# devBoard.net
KiCad netlist of a schematic drawn in Altium Designer
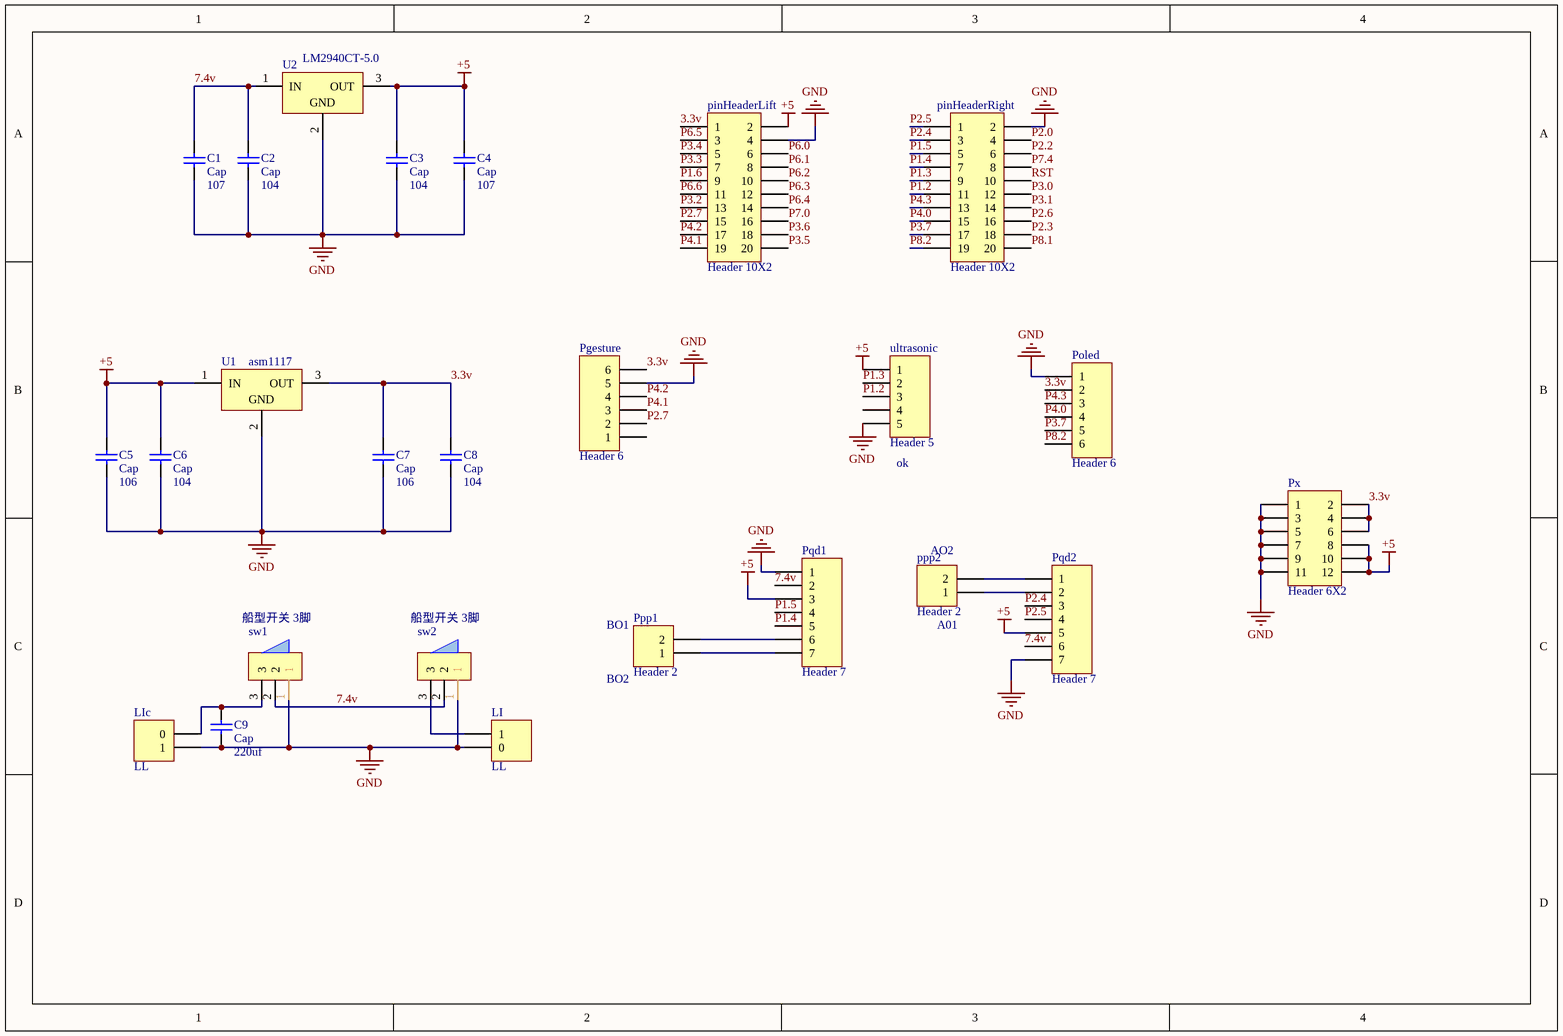
[diagram p0: devBoard.SchDoc]

(export (version "E")
  (design (tool "Eeschema 10.0.6"))
  (components
    (comp (ref "C1")
      (value "Cap")
      (footprint "RAD-0.3")
      (description "Capacitor")
      (fields (field (name "ALTIUM_VALUE") "107") (field (name "PUBLISHER") "Altium Limited"))
      (libsource (lib "Miscellaneous Devices") (part "Cap"))
    )
    (comp (ref "C2")
      (value "Cap")
      (footprint "RAD-0.3")
      (description "Capacitor")
      (fields (field (name "ALTIUM_VALUE") "104") (field (name "PUBLISHER") "Altium Limited"))
      (libsource (lib "Miscellaneous Devices") (part "Cap"))
    )
    (comp (ref "C3")
      (value "Cap")
      (footprint "RAD-0.3")
      (description "Capacitor")
      (fields (field (name "ALTIUM_VALUE") "104") (field (name "PUBLISHER") "Altium Limited"))
      (libsource (lib "Miscellaneous Devices") (part "Cap"))
    )
    (comp (ref "C4")
      (value "Cap")
      (footprint "RAD-0.3")
      (description "Capacitor")
      (fields (field (name "ALTIUM_VALUE") "107") (field (name "PUBLISHER") "Altium Limited"))
      (libsource (lib "Miscellaneous Devices") (part "Cap"))
    )
    (comp (ref "C5")
      (value "Cap")
      (footprint "RAD-0.3")
      (description "Capacitor")
      (fields (field (name "ALTIUM_VALUE") "106") (field (name "PUBLISHER") "Altium Limited"))
      (libsource (lib "Miscellaneous Devices") (part "Cap"))
    )
    (comp (ref "C6")
      (value "Cap")
      (footprint "RAD-0.3")
      (description "Capacitor")
      (fields (field (name "ALTIUM_VALUE") "104") (field (name "PUBLISHER") "Altium Limited"))
      (libsource (lib "Miscellaneous Devices") (part "Cap"))
    )
    (comp (ref "C7")
      (value "Cap")
      (footprint "RAD-0.3")
      (description "Capacitor")
      (fields (field (name "ALTIUM_VALUE") "106") (field (name "PUBLISHER") "Altium Limited"))
      (libsource (lib "Miscellaneous Devices") (part "Cap"))
    )
    (comp (ref "C8")
      (value "Cap")
      (footprint "RAD-0.3")
      (description "Capacitor")
      (fields (field (name "ALTIUM_VALUE") "104") (field (name "PUBLISHER") "Altium Limited"))
      (libsource (lib "Miscellaneous Devices") (part "Cap"))
    )
    (comp (ref "C9")
      (value "Cap")
      (footprint "RAD-0.3")
      (description "Capacitor")
      (fields (field (name "ALTIUM_VALUE") "220uf") (field (name "PUBLISHER") "Altium Limited"))
      (libsource (lib "Miscellaneous Devices") (part "Cap"))
    )
    (comp (ref "LI")
      (value "LL")
      (footprint "Con 2接线端子")
      (description "Header, 2-Pin")
      (fields (field (name "PUBLISHER") "Altium Limited"))
      (libsource (lib "") (part "Header 2_2"))
    )
    (comp (ref "LIc")
      (value "LL")
      (footprint "Con 2接线端子")
      (description "Header, 2-Pin")
      (fields (field (name "PUBLISHER") "Altium Limited"))
      (libsource (lib "") (part "Header 2_1"))
    )
    (comp (ref "Pgesture")
      (value "Header 6")
      (footprint "HDR1X6")
      (description "Header, 6-Pin")
      (fields (field (name "PUBLISHER") "Altium Limited"))
      (libsource (lib "") (part "Header 6_1"))
    )
    (comp (ref "pinHeaderLift")
      (value "Header 10X2")
      (footprint "HDR2X10")
      (description "Header, 10-Pin, Dual row")
      (fields (field (name "PUBLISHER") "Altium Limited"))
      (libsource (lib "Miscellaneous Connectors") (part "Header 10X2"))
    )
    (comp (ref "pinHeaderRight")
      (value "Header 10X2")
      (footprint "HDR2X10")
      (description "Header, 10-Pin, Dual row")
      (fields (field (name "PUBLISHER") "Altium Limited"))
      (libsource (lib "Miscellaneous Connectors") (part "Header 10X2"))
    )
    (comp (ref "Poled")
      (value "Header 6")
      (footprint "HDR1X6")
      (description "Header, 6-Pin")
      (fields (field (name "PUBLISHER") "Altium Limited"))
      (libsource (lib "Miscellaneous Connectors") (part "Header 6"))
    )
    (comp (ref "Ppp1")
      (value "Header 2")
      (footprint "HDR1X2")
      (description "Header, 2-Pin")
      (fields (field (name "PUBLISHER") "Altium Limited"))
      (libsource (lib "Miscellaneous Connectors") (part "Header 2"))
    )
    (comp (ref "ppp2")
      (value "Header 2")
      (footprint "HDR1X2")
      (description "Header, 2-Pin")
      (fields (field (name "PUBLISHER") "Altium Limited"))
      (libsource (lib "Miscellaneous Connectors") (part "Header 2"))
    )
    (comp (ref "Pqd1")
      (value "Header 7")
      (footprint "HDR1X7")
      (description "Header, 7-Pin")
      (fields (field (name "PUBLISHER") "Altium Limited"))
      (libsource (lib "Miscellaneous Connectors") (part "Header 7"))
    )
    (comp (ref "Pqd2")
      (value "Header 7")
      (footprint "HDR1X7")
      (description "Header, 7-Pin")
      (fields (field (name "PUBLISHER") "Altium Limited"))
      (libsource (lib "Miscellaneous Connectors") (part "Header 7"))
    )
    (comp (ref "Px")
      (value "Header 6X2")
      (footprint "HDR2X6")
      (description "Header, 6-Pin, Dual row")
      (fields (field (name "PUBLISHER") "Altium Limited"))
      (libsource (lib "Miscellaneous Connectors") (part "Header 6X2"))
    )
    (comp (ref "sw1")
      (value "船型开关 3脚")
      (footprint "船型开关 3脚")
      (libsource (lib "altium-import") (part "root_0_船型开关 3脚_"))
    )
    (comp (ref "sw2")
      (value "船型开关 3脚")
      (footprint "船型开关 3脚")
      (libsource (lib "altium-import") (part "root_0_船型开关 3脚_"))
    )
    (comp (ref "U1")
      (value "asm1117")
      (footprint "T03B")
      (description "1A 5V")
      (fields (field (name "PUBLISHER") "Altium Limited"))
      (libsource (lib "TSLone") (part "LM2940CT-5.0"))
    )
    (comp (ref "U2")
      (value "LM2940CT-5.0")
      (footprint "T03B")
      (description "1A 5V")
      (fields (field (name "PUBLISHER") "Altium Limited"))
      (libsource (lib "TSLone") (part "LM2940CT-5.0"))
    )
    (comp (ref "ultrasonic")
      (value "Header 5")
      (footprint "HDR1X5")
      (description "Header, 5-Pin")
      (fields (field (name "PUBLISHER") "Altium Limited"))
      (libsource (lib "Miscellaneous Connectors") (part "Header 5"))
    )
  )
  (nets
    (net (code "1") (name "+5") (class "Default")
      (node (ref "C3") (pin "2") (pinfunction "2_2") (pintype "passive"))
      (node (ref "C4") (pin "2") (pinfunction "2_2") (pintype "passive"))
      (node (ref "C5") (pin "2") (pinfunction "2_2") (pintype "passive"))
      (node (ref "C6") (pin "2") (pinfunction "2_2") (pintype "passive"))
      (node (ref "Pqd1") (pin "3") (pinfunction "3_3") (pintype "passive"))
      (node (ref "Pqd2") (pin "5") (pinfunction "5_5") (pintype "passive"))
      (node (ref "Px") (pin "10") (pinfunction "10_10") (pintype "passive"))
      (node (ref "Px") (pin "12") (pinfunction "12_12") (pintype "passive"))
      (node (ref "Px") (pin "8") (pinfunction "8_8") (pintype "passive"))
      (node (ref "U1") (pin "1") (pinfunction "IN_1") (pintype "power_in"))
      (node (ref "U2") (pin "3") (pinfunction "OUT_3") (pintype "power_in"))
      (node (ref "pinHeaderLift") (pin "2") (pinfunction "2_2") (pintype "passive"))
      (node (ref "ultrasonic") (pin "1") (pinfunction "1_1") (pintype "passive"))
    )
    (net (code "2") (name "/3.3v") (class "Default")
      (node (ref "C7") (pin "2") (pinfunction "2_2") (pintype "passive"))
      (node (ref "C8") (pin "2") (pinfunction "2_2") (pintype "passive"))
      (node (ref "Pgesture") (pin "6") (pinfunction "6_6") (pintype "passive"))
      (node (ref "Poled") (pin "2") (pinfunction "2_2") (pintype "passive"))
      (node (ref "Px") (pin "2") (pinfunction "2_2") (pintype "passive"))
      (node (ref "Px") (pin "4") (pinfunction "4_4") (pintype "passive"))
      (node (ref "Px") (pin "6") (pinfunction "6_6") (pintype "passive"))
      (node (ref "U1") (pin "3") (pinfunction "OUT_3") (pintype "power_in"))
      (node (ref "pinHeaderLift") (pin "1") (pinfunction "1_1") (pintype "passive"))
    )
    (net (code "3") (name "/7.4v") (class "Default")
      (node (ref "C1") (pin "2") (pinfunction "2_2") (pintype "passive"))
      (node (ref "C2") (pin "2") (pinfunction "2_2") (pintype "passive"))
      (node (ref "Pqd1") (pin "2") (pinfunction "2_2") (pintype "passive"))
      (node (ref "Pqd2") (pin "6") (pinfunction "6_6") (pintype "passive"))
      (node (ref "U2") (pin "1") (pinfunction "IN_1") (pintype "power_in"))
      (node (ref "sw1") (pin "2") (pinfunction "2_2") (pintype "passive"))
      (node (ref "sw2") (pin "2") (pinfunction "2_2") (pintype "passive"))
    )
    (net (code "4") (name "/P1.2") (class "Default")
      (node (ref "pinHeaderRight") (pin "11") (pinfunction "11_11") (pintype "passive"))
      (node (ref "ultrasonic") (pin "3") (pinfunction "3_3") (pintype "passive"))
    )
    (net (code "5") (name "/P1.3") (class "Default")
      (node (ref "pinHeaderRight") (pin "9") (pinfunction "9_9") (pintype "passive"))
      (node (ref "ultrasonic") (pin "2") (pinfunction "2_2") (pintype "passive"))
    )
    (net (code "6") (name "/P1.4") (class "Default")
      (node (ref "Pqd1") (pin "5") (pinfunction "5_5") (pintype "passive"))
      (node (ref "pinHeaderRight") (pin "7") (pinfunction "7_7") (pintype "passive"))
    )
    (net (code "7") (name "/P1.5") (class "Default")
      (node (ref "Pqd1") (pin "4") (pinfunction "4_4") (pintype "passive"))
      (node (ref "pinHeaderRight") (pin "5") (pinfunction "5_5") (pintype "passive"))
    )
    (net (code "8") (name "/P1.6") (class "Default")
      (node (ref "pinHeaderLift") (pin "9") (pinfunction "9_9") (pintype "passive"))
    )
    (net (code "9") (name "/P2.0") (class "Default")
      (node (ref "pinHeaderRight") (pin "4") (pinfunction "4_4") (pintype "passive"))
    )
    (net (code "10") (name "/P2.2") (class "Default")
      (node (ref "pinHeaderRight") (pin "6") (pinfunction "6_6") (pintype "passive"))
    )
    (net (code "11") (name "/P2.3") (class "Default")
      (node (ref "pinHeaderRight") (pin "18") (pinfunction "18_18") (pintype "passive"))
    )
    (net (code "12") (name "/P2.4") (class "Default")
      (node (ref "Pqd2") (pin "3") (pinfunction "3_3") (pintype "passive"))
      (node (ref "pinHeaderRight") (pin "3") (pinfunction "3_3") (pintype "passive"))
    )
    (net (code "13") (name "/P2.5") (class "Default")
      (node (ref "Pqd2") (pin "4") (pinfunction "4_4") (pintype "passive"))
      (node (ref "pinHeaderRight") (pin "1") (pinfunction "1_1") (pintype "passive"))
    )
    (net (code "14") (name "/P2.6") (class "Default")
      (node (ref "pinHeaderRight") (pin "16") (pinfunction "16_16") (pintype "passive"))
    )
    (net (code "15") (name "/P2.7") (class "Default")
      (node (ref "Pgesture") (pin "2") (pinfunction "2_2") (pintype "passive"))
      (node (ref "pinHeaderLift") (pin "15") (pinfunction "15_15") (pintype "passive"))
    )
    (net (code "16") (name "/P3.0") (class "Default")
      (node (ref "pinHeaderRight") (pin "12") (pinfunction "12_12") (pintype "passive"))
    )
    (net (code "17") (name "/P3.1") (class "Default")
      (node (ref "pinHeaderRight") (pin "14") (pinfunction "14_14") (pintype "passive"))
    )
    (net (code "18") (name "/P3.2") (class "Default")
      (node (ref "pinHeaderLift") (pin "13") (pinfunction "13_13") (pintype "passive"))
    )
    (net (code "19") (name "/P3.3") (class "Default")
      (node (ref "pinHeaderLift") (pin "7") (pinfunction "7_7") (pintype "passive"))
    )
    (net (code "20") (name "/P3.4") (class "Default")
      (node (ref "pinHeaderLift") (pin "5") (pinfunction "5_5") (pintype "passive"))
    )
    (net (code "21") (name "/P3.5") (class "Default")
      (node (ref "pinHeaderLift") (pin "20") (pinfunction "20_20") (pintype "passive"))
    )
    (net (code "22") (name "/P3.6") (class "Default")
      (node (ref "pinHeaderLift") (pin "18") (pinfunction "18_18") (pintype "passive"))
    )
    (net (code "23") (name "/P3.7") (class "Default")
      (node (ref "Poled") (pin "5") (pinfunction "5_5") (pintype "passive"))
      (node (ref "pinHeaderRight") (pin "17") (pinfunction "17_17") (pintype "passive"))
    )
    (net (code "24") (name "/P4.0") (class "Default")
      (node (ref "Poled") (pin "4") (pinfunction "4_4") (pintype "passive"))
      (node (ref "pinHeaderRight") (pin "15") (pinfunction "15_15") (pintype "passive"))
    )
    (net (code "25") (name "/P4.1") (class "Default")
      (node (ref "Pgesture") (pin "3") (pinfunction "3_3") (pintype "passive"))
      (node (ref "pinHeaderLift") (pin "19") (pinfunction "19_19") (pintype "passive"))
    )
    (net (code "26") (name "/P4.2") (class "Default")
      (node (ref "Pgesture") (pin "4") (pinfunction "4_4") (pintype "passive"))
      (node (ref "pinHeaderLift") (pin "17") (pinfunction "17_17") (pintype "passive"))
    )
    (net (code "27") (name "/P4.3") (class "Default")
      (node (ref "Poled") (pin "3") (pinfunction "3_3") (pintype "passive"))
      (node (ref "pinHeaderRight") (pin "13") (pinfunction "13_13") (pintype "passive"))
    )
    (net (code "28") (name "/P6.0") (class "Default")
      (node (ref "pinHeaderLift") (pin "6") (pinfunction "6_6") (pintype "passive"))
    )
    (net (code "29") (name "/P6.1") (class "Default")
      (node (ref "pinHeaderLift") (pin "8") (pinfunction "8_8") (pintype "passive"))
    )
    (net (code "30") (name "/P6.2") (class "Default")
      (node (ref "pinHeaderLift") (pin "10") (pinfunction "10_10") (pintype "passive"))
    )
    (net (code "31") (name "/P6.3") (class "Default")
      (node (ref "pinHeaderLift") (pin "12") (pinfunction "12_12") (pintype "passive"))
    )
    (net (code "32") (name "/P6.4") (class "Default")
      (node (ref "pinHeaderLift") (pin "14") (pinfunction "14_14") (pintype "passive"))
    )
    (net (code "33") (name "/P6.5") (class "Default")
      (node (ref "pinHeaderLift") (pin "3") (pinfunction "3_3") (pintype "passive"))
    )
    (net (code "34") (name "/P6.6") (class "Default")
      (node (ref "pinHeaderLift") (pin "11") (pinfunction "11_11") (pintype "passive"))
    )
    (net (code "35") (name "/P7.0") (class "Default")
      (node (ref "pinHeaderLift") (pin "16") (pinfunction "16_16") (pintype "passive"))
    )
    (net (code "36") (name "/P7.4") (class "Default")
      (node (ref "pinHeaderRight") (pin "8") (pinfunction "8_8") (pintype "passive"))
    )
    (net (code "37") (name "/P8.1") (class "Default")
      (node (ref "pinHeaderRight") (pin "20") (pinfunction "20_20") (pintype "passive"))
    )
    (net (code "38") (name "/P8.2") (class "Default")
      (node (ref "Poled") (pin "6") (pinfunction "6_6") (pintype "passive"))
      (node (ref "pinHeaderRight") (pin "19") (pinfunction "19_19") (pintype "passive"))
    )
    (net (code "39") (name "/RST") (class "Default")
      (node (ref "pinHeaderRight") (pin "10") (pinfunction "10_10") (pintype "passive"))
    )
    (net (code "40") (name "GND") (class "Default")
      (node (ref "C1") (pin "1") (pinfunction "1_1") (pintype "passive"))
      (node (ref "C2") (pin "1") (pinfunction "1_1") (pintype "passive"))
      (node (ref "C3") (pin "1") (pinfunction "1_1") (pintype "passive"))
      (node (ref "C4") (pin "1") (pinfunction "1_1") (pintype "passive"))
      (node (ref "C5") (pin "1") (pinfunction "1_1") (pintype "passive"))
      (node (ref "C6") (pin "1") (pinfunction "1_1") (pintype "passive"))
      (node (ref "C7") (pin "1") (pinfunction "1_1") (pintype "passive"))
      (node (ref "C8") (pin "1") (pinfunction "1_1") (pintype "passive"))
      (node (ref "C9") (pin "1") (pinfunction "1_1") (pintype "passive"))
      (node (ref "LI") (pin "0") (pinfunction "0_0") (pintype "passive"))
      (node (ref "LIc") (pin "1") (pinfunction "1_1") (pintype "passive"))
      (node (ref "Pgesture") (pin "5") (pinfunction "5_5") (pintype "passive"))
      (node (ref "Poled") (pin "1") (pinfunction "1_1") (pintype "passive"))
      (node (ref "Pqd1") (pin "1") (pinfunction "1_1") (pintype "passive"))
      (node (ref "Pqd2") (pin "7") (pinfunction "7_7") (pintype "passive"))
      (node (ref "Px") (pin "1") (pinfunction "1_1") (pintype "passive"))
      (node (ref "Px") (pin "11") (pinfunction "11_11") (pintype "passive"))
      (node (ref "Px") (pin "3") (pinfunction "3_3") (pintype "passive"))
      (node (ref "Px") (pin "5") (pinfunction "5_5") (pintype "passive"))
      (node (ref "Px") (pin "7") (pinfunction "7_7") (pintype "passive"))
      (node (ref "Px") (pin "9") (pinfunction "9_9") (pintype "passive"))
      (node (ref "U1") (pin "2") (pinfunction "GND_2") (pintype "power_in"))
      (node (ref "U2") (pin "2") (pinfunction "GND_2") (pintype "power_in"))
      (node (ref "pinHeaderLift") (pin "4") (pinfunction "4_4") (pintype "passive"))
      (node (ref "pinHeaderRight") (pin "2") (pinfunction "2_2") (pintype "passive"))
      (node (ref "sw1") (pin "1") (pinfunction "1_1") (pintype "passive"))
      (node (ref "sw2") (pin "1") (pinfunction "1_1") (pintype "passive"))
      (node (ref "ultrasonic") (pin "5") (pinfunction "5_5") (pintype "passive"))
    )
    (net (code "41") (name "Net-(C9-Pad2)") (class "Default")
      (node (ref "C9") (pin "2") (pinfunction "2_2") (pintype "passive"))
      (node (ref "LIc") (pin "0") (pinfunction "0_0") (pintype "passive"))
      (node (ref "sw1") (pin "3") (pinfunction "3_3") (pintype "passive"))
    )
    (net (code "42") (name "Net-(LI-Pad1)") (class "Default")
      (node (ref "LI") (pin "1") (pinfunction "1_1") (pintype "passive"))
      (node (ref "sw2") (pin "3") (pinfunction "3_3") (pintype "passive"))
    )
    (net (code "43") (name "Net-(Ppp1-Pad1)") (class "Default")
      (node (ref "Ppp1") (pin "1") (pinfunction "1_1") (pintype "passive"))
      (node (ref "Pqd1") (pin "7") (pinfunction "7_7") (pintype "passive"))
    )
    (net (code "44") (name "Net-(Ppp1-Pad2)") (class "Default")
      (node (ref "Ppp1") (pin "2") (pinfunction "2_2") (pintype "passive"))
      (node (ref "Pqd1") (pin "6") (pinfunction "6_6") (pintype "passive"))
    )
    (net (code "45") (name "Net-(Pqd2-Pad1)") (class "Default")
      (node (ref "Pqd2") (pin "1") (pinfunction "1_1") (pintype "passive"))
      (node (ref "ppp2") (pin "2") (pinfunction "2_2") (pintype "passive"))
    )
    (net (code "46") (name "Net-(Pqd2-Pad2)") (class "Default")
      (node (ref "Pqd2") (pin "2") (pinfunction "2_2") (pintype "passive"))
      (node (ref "ppp2") (pin "1") (pinfunction "1_1") (pintype "passive"))
    )
    (net (code "47") (name "unconnected-(Pgesture-Pad1)") (class "Default")
      (node (ref "Pgesture") (pin "1") (pinfunction "1_1") (pintype "passive"))
    )
    (net (code "48") (name "unconnected-(ultrasonic-Pad4)") (class "Default")
      (node (ref "ultrasonic") (pin "4") (pinfunction "4_4") (pintype "passive"))
    )
  )
)
